# Pianissimo.net
KiCad netlist of a schematic drawn in EAGLE
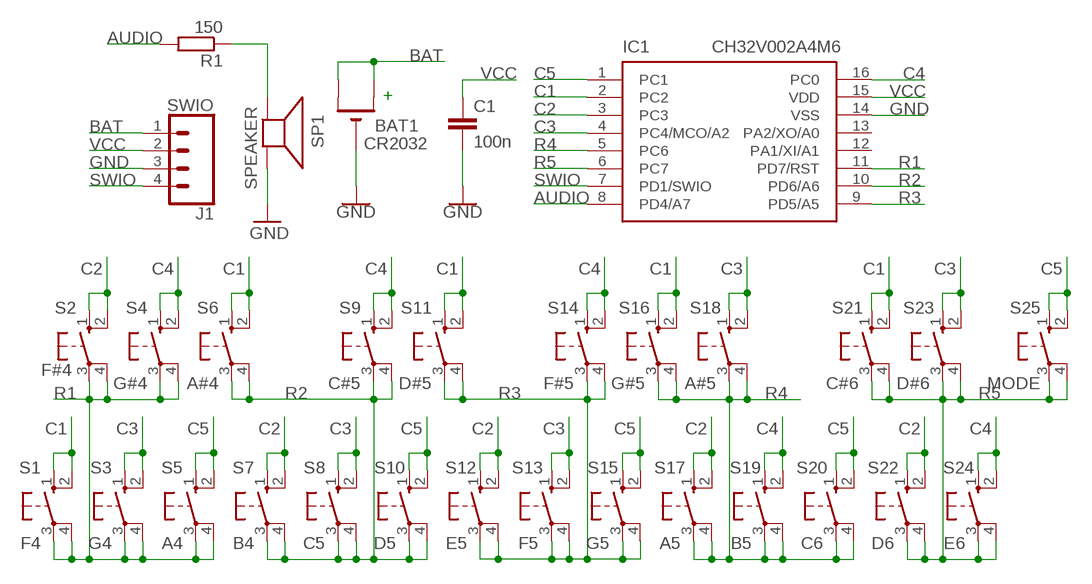
[diagram p0: schematic, sheet 1]

(export (version "E")
  (design (tool "Eeschema 10.0.6"))
  (components
    (comp (ref "BAT1")
      (value "CR2032")
      (footprint "eagle-import:CR2032-THRU")
      (libsource (lib "eagle-import") (part "CR2032THM"))
    )
    (comp (ref "C1")
      (value "100n")
      (footprint "eagle-import:C050-024X044")
      (libsource (lib "eagle-import") (part "C-EU050-024X044"))
    )
    (comp (ref "IC1")
      (value "CH32V002A4M6")
      (footprint "eagle-import:SOP16")
      (libsource (lib "eagle-import") (part "CH32V002A4M6"))
    )
    (comp (ref "J1")
      (value "SWIO")
      (footprint "eagle-import:1X04_LONGPADS")
      (libsource (lib "eagle-import") (part "CONN_04LONGPADS"))
    )
    (comp (ref "R1")
      (value "150")
      (footprint "eagle-import:0204_7")
      (libsource (lib "eagle-import") (part "R-EU_0204/7"))
    )
    (comp (ref "S1")
      (value "F4")
      (footprint "eagle-import:B3F-10XX")
      (fields (field (name "MPN") "B3F-1000"))
      (libsource (lib "eagle-import") (part "10-XX"))
    )
    (comp (ref "S2")
      (value "F#4")
      (footprint "eagle-import:B3F-10XX")
      (fields (field (name "MPN") "B3F-1000"))
      (libsource (lib "eagle-import") (part "10-XX"))
    )
    (comp (ref "S3")
      (value "G4")
      (footprint "eagle-import:B3F-10XX")
      (fields (field (name "MPN") "B3F-1000"))
      (libsource (lib "eagle-import") (part "10-XX"))
    )
    (comp (ref "S4")
      (value "G#4")
      (footprint "eagle-import:B3F-10XX")
      (fields (field (name "MPN") "B3F-1000"))
      (libsource (lib "eagle-import") (part "10-XX"))
    )
    (comp (ref "S5")
      (value "A4")
      (footprint "eagle-import:B3F-10XX")
      (fields (field (name "MPN") "B3F-1000"))
      (libsource (lib "eagle-import") (part "10-XX"))
    )
    (comp (ref "S6")
      (value "A#4")
      (footprint "eagle-import:B3F-10XX")
      (fields (field (name "MPN") "B3F-1000"))
      (libsource (lib "eagle-import") (part "10-XX"))
    )
    (comp (ref "S7")
      (value "B4")
      (footprint "eagle-import:B3F-10XX")
      (fields (field (name "MPN") "B3F-1000"))
      (libsource (lib "eagle-import") (part "10-XX"))
    )
    (comp (ref "S8")
      (value "C5")
      (footprint "eagle-import:B3F-10XX")
      (fields (field (name "MPN") "B3F-1000"))
      (libsource (lib "eagle-import") (part "10-XX"))
    )
    (comp (ref "S9")
      (value "C#5")
      (footprint "eagle-import:B3F-10XX")
      (fields (field (name "MPN") "B3F-1000"))
      (libsource (lib "eagle-import") (part "10-XX"))
    )
    (comp (ref "S10")
      (value "D5")
      (footprint "eagle-import:B3F-10XX")
      (fields (field (name "MPN") "B3F-1000"))
      (libsource (lib "eagle-import") (part "10-XX"))
    )
    (comp (ref "S11")
      (value "D#5")
      (footprint "eagle-import:B3F-10XX")
      (fields (field (name "MPN") "B3F-1000"))
      (libsource (lib "eagle-import") (part "10-XX"))
    )
    (comp (ref "S12")
      (value "E5")
      (footprint "eagle-import:B3F-10XX")
      (fields (field (name "MPN") "B3F-1000"))
      (libsource (lib "eagle-import") (part "10-XX"))
    )
    (comp (ref "S13")
      (value "F5")
      (footprint "eagle-import:B3F-10XX")
      (fields (field (name "MPN") "B3F-1000"))
      (libsource (lib "eagle-import") (part "10-XX"))
    )
    (comp (ref "S14")
      (value "F#5")
      (footprint "eagle-import:B3F-10XX")
      (fields (field (name "MPN") "B3F-1000"))
      (libsource (lib "eagle-import") (part "10-XX"))
    )
    (comp (ref "S15")
      (value "G5")
      (footprint "eagle-import:B3F-10XX")
      (fields (field (name "MPN") "B3F-1000"))
      (libsource (lib "eagle-import") (part "10-XX"))
    )
    (comp (ref "S16")
      (value "G#5")
      (footprint "eagle-import:B3F-10XX")
      (fields (field (name "MPN") "B3F-1000"))
      (libsource (lib "eagle-import") (part "10-XX"))
    )
    (comp (ref "S17")
      (value "A5")
      (footprint "eagle-import:B3F-10XX")
      (fields (field (name "MPN") "B3F-1000"))
      (libsource (lib "eagle-import") (part "10-XX"))
    )
    (comp (ref "S18")
      (value "A#5")
      (footprint "eagle-import:B3F-10XX")
      (fields (field (name "MPN") "B3F-1000"))
      (libsource (lib "eagle-import") (part "10-XX"))
    )
    (comp (ref "S19")
      (value "B5")
      (footprint "eagle-import:B3F-10XX")
      (fields (field (name "MPN") "B3F-1000"))
      (libsource (lib "eagle-import") (part "10-XX"))
    )
    (comp (ref "S20")
      (value "C6")
      (footprint "eagle-import:B3F-10XX")
      (fields (field (name "MPN") "B3F-1000"))
      (libsource (lib "eagle-import") (part "10-XX"))
    )
    (comp (ref "S21")
      (value "C#6")
      (footprint "eagle-import:B3F-10XX")
      (fields (field (name "MPN") "B3F-1000"))
      (libsource (lib "eagle-import") (part "10-XX"))
    )
    (comp (ref "S22")
      (value "D6")
      (footprint "eagle-import:B3F-10XX")
      (fields (field (name "MPN") "B3F-1000"))
      (libsource (lib "eagle-import") (part "10-XX"))
    )
    (comp (ref "S23")
      (value "D#6")
      (footprint "eagle-import:B3F-10XX")
      (fields (field (name "MPN") "B3F-1000"))
      (libsource (lib "eagle-import") (part "10-XX"))
    )
    (comp (ref "S24")
      (value "E6")
      (footprint "eagle-import:B3F-10XX")
      (fields (field (name "MPN") "B3F-1000"))
      (libsource (lib "eagle-import") (part "10-XX"))
    )
    (comp (ref "S25")
      (value "MODE")
      (footprint "eagle-import:B3F-10XX")
      (fields (field (name "MPN") "B3F-1000"))
      (libsource (lib "eagle-import") (part "10-XX"))
    )
    (comp (ref "SP1")
      (value "SPEAKER")
      (footprint "eagle-import:AL60P")
      (libsource (lib "eagle-import") (part "SPEAKER/AL60P"))
    )
  )
  (nets
    (net (code "1") (name "/AUDIO") (class "Default")
      (node (ref "IC1") (pin "8") (pinfunction "PD4/A7_8") (pintype "bidirectional"))
      (node (ref "R1") (pin "2") (pinfunction "2_2") (pintype "passive"))
    )
    (net (code "2") (name "/BAT") (class "Default")
      (node (ref "BAT1") (pin "+1") (pinfunction "+_+1") (pintype "passive"))
      (node (ref "BAT1") (pin "+2") (pinfunction "+1_+2") (pintype "passive"))
      (node (ref "J1") (pin "1") (pinfunction "1_1") (pintype "passive"))
    )
    (net (code "3") (name "/C1") (class "Default")
      (node (ref "IC1") (pin "2") (pinfunction "PC2_2") (pintype "bidirectional"))
      (node (ref "S1") (pin "1") (pinfunction "S_1") (pintype "passive"))
      (node (ref "S1") (pin "2") (pinfunction "S1_2") (pintype "passive"))
      (node (ref "S11") (pin "1") (pinfunction "S_1") (pintype "passive"))
      (node (ref "S11") (pin "2") (pinfunction "S1_2") (pintype "passive"))
      (node (ref "S16") (pin "1") (pinfunction "S_1") (pintype "passive"))
      (node (ref "S16") (pin "2") (pinfunction "S1_2") (pintype "passive"))
      (node (ref "S21") (pin "1") (pinfunction "S_1") (pintype "passive"))
      (node (ref "S21") (pin "2") (pinfunction "S1_2") (pintype "passive"))
      (node (ref "S6") (pin "1") (pinfunction "S_1") (pintype "passive"))
      (node (ref "S6") (pin "2") (pinfunction "S1_2") (pintype "passive"))
    )
    (net (code "4") (name "/C2") (class "Default")
      (node (ref "IC1") (pin "3") (pinfunction "PC3_3") (pintype "bidirectional"))
      (node (ref "S12") (pin "1") (pinfunction "S_1") (pintype "passive"))
      (node (ref "S12") (pin "2") (pinfunction "S1_2") (pintype "passive"))
      (node (ref "S17") (pin "1") (pinfunction "S_1") (pintype "passive"))
      (node (ref "S17") (pin "2") (pinfunction "S1_2") (pintype "passive"))
      (node (ref "S2") (pin "1") (pinfunction "S_1") (pintype "passive"))
      (node (ref "S2") (pin "2") (pinfunction "S1_2") (pintype "passive"))
      (node (ref "S22") (pin "1") (pinfunction "S_1") (pintype "passive"))
      (node (ref "S22") (pin "2") (pinfunction "S1_2") (pintype "passive"))
      (node (ref "S7") (pin "1") (pinfunction "S_1") (pintype "passive"))
      (node (ref "S7") (pin "2") (pinfunction "S1_2") (pintype "passive"))
    )
    (net (code "5") (name "/C3") (class "Default")
      (node (ref "IC1") (pin "4") (pinfunction "PC4/MCO/A2_4") (pintype "bidirectional"))
      (node (ref "S13") (pin "1") (pinfunction "S_1") (pintype "passive"))
      (node (ref "S13") (pin "2") (pinfunction "S1_2") (pintype "passive"))
      (node (ref "S18") (pin "1") (pinfunction "S_1") (pintype "passive"))
      (node (ref "S18") (pin "2") (pinfunction "S1_2") (pintype "passive"))
      (node (ref "S23") (pin "1") (pinfunction "S_1") (pintype "passive"))
      (node (ref "S23") (pin "2") (pinfunction "S1_2") (pintype "passive"))
      (node (ref "S3") (pin "1") (pinfunction "S_1") (pintype "passive"))
      (node (ref "S3") (pin "2") (pinfunction "S1_2") (pintype "passive"))
      (node (ref "S8") (pin "1") (pinfunction "S_1") (pintype "passive"))
      (node (ref "S8") (pin "2") (pinfunction "S1_2") (pintype "passive"))
    )
    (net (code "6") (name "/C4") (class "Default")
      (node (ref "IC1") (pin "16") (pinfunction "PC0_16") (pintype "bidirectional"))
      (node (ref "S14") (pin "1") (pinfunction "S_1") (pintype "passive"))
      (node (ref "S14") (pin "2") (pinfunction "S1_2") (pintype "passive"))
      (node (ref "S19") (pin "1") (pinfunction "S_1") (pintype "passive"))
      (node (ref "S19") (pin "2") (pinfunction "S1_2") (pintype "passive"))
      (node (ref "S24") (pin "1") (pinfunction "S_1") (pintype "passive"))
      (node (ref "S24") (pin "2") (pinfunction "S1_2") (pintype "passive"))
      (node (ref "S4") (pin "1") (pinfunction "S_1") (pintype "passive"))
      (node (ref "S4") (pin "2") (pinfunction "S1_2") (pintype "passive"))
      (node (ref "S9") (pin "1") (pinfunction "S_1") (pintype "passive"))
      (node (ref "S9") (pin "2") (pinfunction "S1_2") (pintype "passive"))
    )
    (net (code "7") (name "/C5") (class "Default")
      (node (ref "IC1") (pin "1") (pinfunction "PC1_1") (pintype "bidirectional"))
      (node (ref "S10") (pin "1") (pinfunction "S_1") (pintype "passive"))
      (node (ref "S10") (pin "2") (pinfunction "S1_2") (pintype "passive"))
      (node (ref "S15") (pin "1") (pinfunction "S_1") (pintype "passive"))
      (node (ref "S15") (pin "2") (pinfunction "S1_2") (pintype "passive"))
      (node (ref "S20") (pin "1") (pinfunction "S_1") (pintype "passive"))
      (node (ref "S20") (pin "2") (pinfunction "S1_2") (pintype "passive"))
      (node (ref "S25") (pin "1") (pinfunction "S_1") (pintype "passive"))
      (node (ref "S25") (pin "2") (pinfunction "S1_2") (pintype "passive"))
      (node (ref "S5") (pin "1") (pinfunction "S_1") (pintype "passive"))
      (node (ref "S5") (pin "2") (pinfunction "S1_2") (pintype "passive"))
    )
    (net (code "8") (name "/R1") (class "Default")
      (node (ref "IC1") (pin "11") (pinfunction "PD7/RST_11") (pintype "bidirectional"))
      (node (ref "S1") (pin "3") (pinfunction "P_3") (pintype "passive"))
      (node (ref "S1") (pin "4") (pinfunction "P1_4") (pintype "passive"))
      (node (ref "S2") (pin "3") (pinfunction "P_3") (pintype "passive"))
      (node (ref "S2") (pin "4") (pinfunction "P1_4") (pintype "passive"))
      (node (ref "S3") (pin "3") (pinfunction "P_3") (pintype "passive"))
      (node (ref "S3") (pin "4") (pinfunction "P1_4") (pintype "passive"))
      (node (ref "S4") (pin "3") (pinfunction "P_3") (pintype "passive"))
      (node (ref "S4") (pin "4") (pinfunction "P1_4") (pintype "passive"))
      (node (ref "S5") (pin "3") (pinfunction "P_3") (pintype "passive"))
      (node (ref "S5") (pin "4") (pinfunction "P1_4") (pintype "passive"))
    )
    (net (code "9") (name "/R2") (class "Default")
      (node (ref "IC1") (pin "10") (pinfunction "PD6/A6_10") (pintype "bidirectional"))
      (node (ref "S10") (pin "3") (pinfunction "P_3") (pintype "passive"))
      (node (ref "S10") (pin "4") (pinfunction "P1_4") (pintype "passive"))
      (node (ref "S6") (pin "3") (pinfunction "P_3") (pintype "passive"))
      (node (ref "S6") (pin "4") (pinfunction "P1_4") (pintype "passive"))
      (node (ref "S7") (pin "3") (pinfunction "P_3") (pintype "passive"))
      (node (ref "S7") (pin "4") (pinfunction "P1_4") (pintype "passive"))
      (node (ref "S8") (pin "3") (pinfunction "P_3") (pintype "passive"))
      (node (ref "S8") (pin "4") (pinfunction "P1_4") (pintype "passive"))
      (node (ref "S9") (pin "3") (pinfunction "P_3") (pintype "passive"))
      (node (ref "S9") (pin "4") (pinfunction "P1_4") (pintype "passive"))
    )
    (net (code "10") (name "/R3") (class "Default")
      (node (ref "IC1") (pin "9") (pinfunction "PD5/A5_9") (pintype "bidirectional"))
      (node (ref "S11") (pin "3") (pinfunction "P_3") (pintype "passive"))
      (node (ref "S11") (pin "4") (pinfunction "P1_4") (pintype "passive"))
      (node (ref "S12") (pin "3") (pinfunction "P_3") (pintype "passive"))
      (node (ref "S12") (pin "4") (pinfunction "P1_4") (pintype "passive"))
      (node (ref "S13") (pin "3") (pinfunction "P_3") (pintype "passive"))
      (node (ref "S13") (pin "4") (pinfunction "P1_4") (pintype "passive"))
      (node (ref "S14") (pin "3") (pinfunction "P_3") (pintype "passive"))
      (node (ref "S14") (pin "4") (pinfunction "P1_4") (pintype "passive"))
      (node (ref "S15") (pin "3") (pinfunction "P_3") (pintype "passive"))
      (node (ref "S15") (pin "4") (pinfunction "P1_4") (pintype "passive"))
    )
    (net (code "11") (name "/R4") (class "Default")
      (node (ref "IC1") (pin "5") (pinfunction "PC6_5") (pintype "bidirectional"))
      (node (ref "S16") (pin "3") (pinfunction "P_3") (pintype "passive"))
      (node (ref "S16") (pin "4") (pinfunction "P1_4") (pintype "passive"))
      (node (ref "S17") (pin "3") (pinfunction "P_3") (pintype "passive"))
      (node (ref "S17") (pin "4") (pinfunction "P1_4") (pintype "passive"))
      (node (ref "S18") (pin "3") (pinfunction "P_3") (pintype "passive"))
      (node (ref "S18") (pin "4") (pinfunction "P1_4") (pintype "passive"))
      (node (ref "S19") (pin "3") (pinfunction "P_3") (pintype "passive"))
      (node (ref "S19") (pin "4") (pinfunction "P1_4") (pintype "passive"))
      (node (ref "S20") (pin "3") (pinfunction "P_3") (pintype "passive"))
      (node (ref "S20") (pin "4") (pinfunction "P1_4") (pintype "passive"))
    )
    (net (code "12") (name "/R5") (class "Default")
      (node (ref "IC1") (pin "6") (pinfunction "PC7_6") (pintype "bidirectional"))
      (node (ref "S21") (pin "3") (pinfunction "P_3") (pintype "passive"))
      (node (ref "S21") (pin "4") (pinfunction "P1_4") (pintype "passive"))
      (node (ref "S22") (pin "3") (pinfunction "P_3") (pintype "passive"))
      (node (ref "S22") (pin "4") (pinfunction "P1_4") (pintype "passive"))
      (node (ref "S23") (pin "3") (pinfunction "P_3") (pintype "passive"))
      (node (ref "S23") (pin "4") (pinfunction "P1_4") (pintype "passive"))
      (node (ref "S24") (pin "3") (pinfunction "P_3") (pintype "passive"))
      (node (ref "S24") (pin "4") (pinfunction "P1_4") (pintype "passive"))
      (node (ref "S25") (pin "3") (pinfunction "P_3") (pintype "passive"))
      (node (ref "S25") (pin "4") (pinfunction "P1_4") (pintype "passive"))
    )
    (net (code "13") (name "/SWIO") (class "Default")
      (node (ref "IC1") (pin "7") (pinfunction "PD1/SWIO_7") (pintype "bidirectional"))
      (node (ref "J1") (pin "4") (pinfunction "4_4") (pintype "passive"))
    )
    (net (code "14") (name "/VCC") (class "Default")
      (node (ref "C1") (pin "1") (pinfunction "1_1") (pintype "passive"))
      (node (ref "IC1") (pin "15") (pinfunction "VDD_15") (pintype "power_in"))
      (node (ref "J1") (pin "2") (pinfunction "2_2") (pintype "passive"))
    )
    (net (code "15") (name "GND") (class "Default")
      (node (ref "BAT1") (pin "-") (pinfunction "-_-") (pintype "passive"))
      (node (ref "C1") (pin "2") (pinfunction "2_2") (pintype "passive"))
      (node (ref "IC1") (pin "14") (pinfunction "VSS_14") (pintype "power_in"))
      (node (ref "J1") (pin "3") (pinfunction "3_3") (pintype "passive"))
      (node (ref "SP1") (pin "2") (pinfunction "-_2") (pintype "passive"))
    )
    (net (code "16") (name "Net-(SP1-+)") (class "Default")
      (node (ref "R1") (pin "1") (pinfunction "1_1") (pintype "passive"))
      (node (ref "SP1") (pin "1") (pinfunction "+_1") (pintype "passive"))
    )
    (net (code "17") (name "unconnected-(IC1-PA1{slash}XI{slash}A1-Pad12)") (class "Default")
      (node (ref "IC1") (pin "12") (pinfunction "PA1/XI/A1_12") (pintype "bidirectional"))
    )
    (net (code "18") (name "unconnected-(IC1-PA2{slash}XO{slash}A0-Pad13)") (class "Default")
      (node (ref "IC1") (pin "13") (pinfunction "PA2/XO/A0_13") (pintype "bidirectional"))
    )
  )
)
